# button.net
KiCad netlist of a schematic drawn in EAGLE
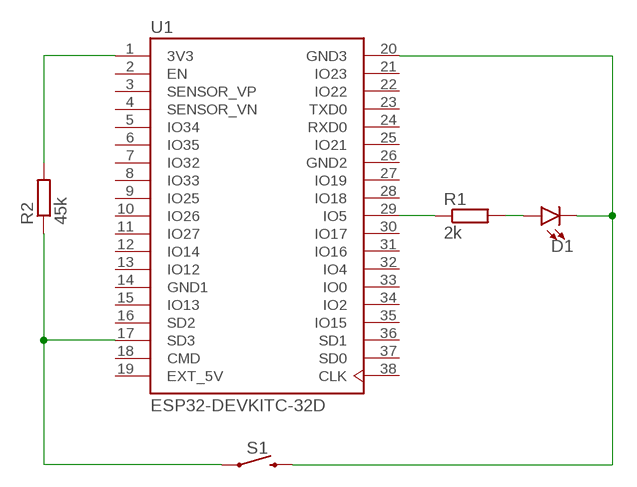
[diagram p0: schematic, sheet 1]

(export (version "E")
  (design (tool "Eeschema 10.0.6"))
  (components
    (comp (ref "D1")
      (value "LED5MM")
      (footprint "eagle-import:LED_5MM")
      (libsource (lib "eagle-import") (part "LED5MM"))
    )
    (comp (ref "R1")
      (value "2k")
      (footprint "eagle-import:0204_7")
      (libsource (lib "eagle-import") (part "R-EU_0204/7"))
    )
    (comp (ref "R2")
      (value "45k")
      (footprint "eagle-import:0204_5")
      (libsource (lib "eagle-import") (part "resistor_348_R-EU_0204/5"))
    )
    (comp (ref "S1")
      (value "MOMENTARY-SWITCH-SPST-PTH-6.0MM")
      (footprint "eagle-import:TACTILE_SWITCH_PTH_6.0MM")
      (libsource (lib "eagle-import") (part "MOMENTARY-SWITCH-SPST-PTH-6.0MM"))
    )
    (comp (ref "U1")
      (value "ESP32-DEVKITC-32D")
      (footprint "eagle-import:MODULE_ESP32-DEVKITC-32D")
      (fields (field (name "MF") "Espressif Systems"))
      (libsource (lib "eagle-import") (part "ESP32-DEVKITC-32D"))
    )
  )
  (nets
    (net (code "1") (name "/EXT_5V") (class "Default")
      (node (ref "U1") (pin "19") (pinfunction "EXT_5V_19") (pintype "power_in"))
    )
    (net (code "2") (name "/GND1") (class "Default")
      (node (ref "U1") (pin "14") (pinfunction "GND1_14") (pintype "power_in"))
    )
    (net (code "3") (name "/GND2") (class "Default")
      (node (ref "U1") (pin "26") (pinfunction "GND2_26") (pintype "power_in"))
    )
    (net (code "4") (name "Net-(D1-C)") (class "Default")
      (node (ref "D1") (pin "K") (pinfunction "C_K") (pintype "passive"))
      (node (ref "S1") (pin "3") (pinfunction "2_3") (pintype "passive"))
      (node (ref "U1") (pin "20") (pinfunction "GND3_20") (pintype "power_in"))
    )
    (net (code "5") (name "Net-(D1-PadA)") (class "Default")
      (node (ref "D1") (pin "A") (pinfunction "A_A") (pintype "passive"))
      (node (ref "R1") (pin "2") (pinfunction "2_2") (pintype "passive"))
    )
    (net (code "6") (name "Net-(U1-3V3)") (class "Default")
      (node (ref "R2") (pin "2") (pinfunction "2_2") (pintype "passive"))
      (node (ref "U1") (pin "1") (pinfunction "3V3_1") (pintype "power_in"))
    )
    (net (code "7") (name "Net-(U1-IO5)") (class "Default")
      (node (ref "R1") (pin "1") (pinfunction "1_1") (pintype "passive"))
      (node (ref "U1") (pin "29") (pinfunction "IO5_29") (pintype "bidirectional"))
    )
    (net (code "8") (name "Net-(U1-SD3)") (class "Default")
      (node (ref "R2") (pin "1") (pinfunction "1_1") (pintype "passive"))
      (node (ref "S1") (pin "1") (pinfunction "1_1") (pintype "passive"))
      (node (ref "U1") (pin "17") (pinfunction "SD3_17") (pintype "bidirectional"))
    )
    (net (code "9") (name "unconnected-(U1-CLK-Pad38)") (class "Default")
      (node (ref "U1") (pin "38") (pinfunction "CLK_38") (pintype "input"))
    )
    (net (code "10") (name "unconnected-(U1-CMD-Pad18)") (class "Default")
      (node (ref "U1") (pin "18") (pinfunction "CMD_18") (pintype "bidirectional"))
    )
    (net (code "11") (name "unconnected-(U1-EN-Pad2)") (class "Default")
      (node (ref "U1") (pin "2") (pinfunction "EN_2") (pintype "input"))
    )
    (net (code "12") (name "unconnected-(U1-IO0-Pad33)") (class "Default")
      (node (ref "U1") (pin "33") (pinfunction "IO0_33") (pintype "bidirectional"))
    )
    (net (code "13") (name "unconnected-(U1-IO2-Pad34)") (class "Default")
      (node (ref "U1") (pin "34") (pinfunction "IO2_34") (pintype "bidirectional"))
    )
    (net (code "14") (name "unconnected-(U1-IO4-Pad32)") (class "Default")
      (node (ref "U1") (pin "32") (pinfunction "IO4_32") (pintype "bidirectional"))
    )
    (net (code "15") (name "unconnected-(U1-IO12-Pad13)") (class "Default")
      (node (ref "U1") (pin "13") (pinfunction "IO12_13") (pintype "bidirectional"))
    )
    (net (code "16") (name "unconnected-(U1-IO13-Pad15)") (class "Default")
      (node (ref "U1") (pin "15") (pinfunction "IO13_15") (pintype "bidirectional"))
    )
    (net (code "17") (name "unconnected-(U1-IO14-Pad12)") (class "Default")
      (node (ref "U1") (pin "12") (pinfunction "IO14_12") (pintype "bidirectional"))
    )
    (net (code "18") (name "unconnected-(U1-IO15-Pad35)") (class "Default")
      (node (ref "U1") (pin "35") (pinfunction "IO15_35") (pintype "bidirectional"))
    )
    (net (code "19") (name "unconnected-(U1-IO16-Pad31)") (class "Default")
      (node (ref "U1") (pin "31") (pinfunction "IO16_31") (pintype "bidirectional"))
    )
    (net (code "20") (name "unconnected-(U1-IO17-Pad30)") (class "Default")
      (node (ref "U1") (pin "30") (pinfunction "IO17_30") (pintype "bidirectional"))
    )
    (net (code "21") (name "unconnected-(U1-IO18-Pad28)") (class "Default")
      (node (ref "U1") (pin "28") (pinfunction "IO18_28") (pintype "bidirectional"))
    )
    (net (code "22") (name "unconnected-(U1-IO19-Pad27)") (class "Default")
      (node (ref "U1") (pin "27") (pinfunction "IO19_27") (pintype "bidirectional"))
    )
    (net (code "23") (name "unconnected-(U1-IO21-Pad25)") (class "Default")
      (node (ref "U1") (pin "25") (pinfunction "IO21_25") (pintype "bidirectional"))
    )
    (net (code "24") (name "unconnected-(U1-IO22-Pad22)") (class "Default")
      (node (ref "U1") (pin "22") (pinfunction "IO22_22") (pintype "bidirectional"))
    )
    (net (code "25") (name "unconnected-(U1-IO23-Pad21)") (class "Default")
      (node (ref "U1") (pin "21") (pinfunction "IO23_21") (pintype "bidirectional"))
    )
    (net (code "26") (name "unconnected-(U1-IO25-Pad9)") (class "Default")
      (node (ref "U1") (pin "9") (pinfunction "IO25_9") (pintype "bidirectional"))
    )
    (net (code "27") (name "unconnected-(U1-IO26-Pad10)") (class "Default")
      (node (ref "U1") (pin "10") (pinfunction "IO26_10") (pintype "bidirectional"))
    )
    (net (code "28") (name "unconnected-(U1-IO27-Pad11)") (class "Default")
      (node (ref "U1") (pin "11") (pinfunction "IO27_11") (pintype "bidirectional"))
    )
    (net (code "29") (name "unconnected-(U1-IO32-Pad7)") (class "Default")
      (node (ref "U1") (pin "7") (pinfunction "IO32_7") (pintype "bidirectional"))
    )
    (net (code "30") (name "unconnected-(U1-IO33-Pad8)") (class "Default")
      (node (ref "U1") (pin "8") (pinfunction "IO33_8") (pintype "bidirectional"))
    )
    (net (code "31") (name "unconnected-(U1-IO34-Pad5)") (class "Default")
      (node (ref "U1") (pin "5") (pinfunction "IO34_5") (pintype "bidirectional"))
    )
    (net (code "32") (name "unconnected-(U1-IO35-Pad6)") (class "Default")
      (node (ref "U1") (pin "6") (pinfunction "IO35_6") (pintype "bidirectional"))
    )
    (net (code "33") (name "unconnected-(U1-RXD0-Pad24)") (class "Default")
      (node (ref "U1") (pin "24") (pinfunction "RXD0_24") (pintype "input"))
    )
    (net (code "34") (name "unconnected-(U1-SD0-Pad37)") (class "Default")
      (node (ref "U1") (pin "37") (pinfunction "SD0_37") (pintype "bidirectional"))
    )
    (net (code "35") (name "unconnected-(U1-SD1-Pad36)") (class "Default")
      (node (ref "U1") (pin "36") (pinfunction "SD1_36") (pintype "bidirectional"))
    )
    (net (code "36") (name "unconnected-(U1-SD2-Pad16)") (class "Default")
      (node (ref "U1") (pin "16") (pinfunction "SD2_16") (pintype "bidirectional"))
    )
    (net (code "37") (name "unconnected-(U1-SENSOR_VN-Pad4)") (class "Default")
      (node (ref "U1") (pin "4") (pinfunction "SENSOR_VN_4") (pintype "input"))
    )
    (net (code "38") (name "unconnected-(U1-SENSOR_VP-Pad3)") (class "Default")
      (node (ref "U1") (pin "3") (pinfunction "SENSOR_VP_3") (pintype "input"))
    )
    (net (code "39") (name "unconnected-(U1-TXD0-Pad23)") (class "Default")
      (node (ref "U1") (pin "23") (pinfunction "TXD0_23") (pintype "output"))
    )
  )
)
